# -46342_21-004_3_8.net
KiCad netlist of a schematic drawn in Altium Designer
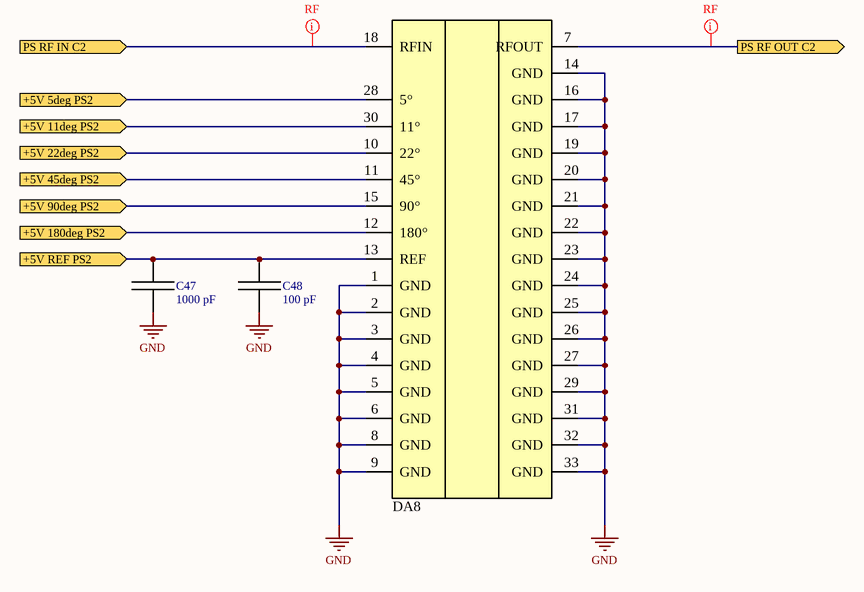
[diagram p0: МПСУ-46342.21-004 Э3 Лист8.SchDoc]

(export (version "E")
  (design (tool "Eeschema 10.0.6"))
  (components
    (comp (ref "C47")
      (value "1000 pF")
      (footprint "CAPC100X50X55L20N")
      (description "Capacitor, generic")
      (fields (field (name "TOLERANCE") "5 %"))
      (libsource (lib "StudentsLibrary") (part "Capacitor"))
    )
    (comp (ref "C48")
      (value "100 pF")
      (footprint "CAPC100X50X55L20N")
      (description "Capacitor, generic")
      (fields (field (name "TOLERANCE") "5 %"))
      (libsource (lib "StudentsLibrary") (part "Capacitor"))
    )
    (comp (ref "DA8")
      (value "TGP2105-SM")
      (footprint "QFN33P50_500X500X80L46X25T340N")
      (description "6 - 18 GHz 6-Bit Digital Phase Shifter (+Vc)")
      (fields (field (name "MANUFACTURER") "Qorvo"))
      (libsource (lib "receiver") (part "TGP2105-SM 1"))
    )
  )
  (nets
    (net (code "1") (name "/+5V 5deg PS2") (class "Default")
      (node (ref "DA8") (pin "28") (pinfunction "5°_28") (pintype "passive"))
    )
    (net (code "2") (name "/+5V 11deg PS2") (class "Default")
      (node (ref "DA8") (pin "30") (pinfunction "11°_30") (pintype "passive"))
    )
    (net (code "3") (name "/+5V 22deg PS2") (class "Default")
      (node (ref "DA8") (pin "10") (pinfunction "22°_10") (pintype "passive"))
    )
    (net (code "4") (name "/+5V 45deg PS2") (class "Default")
      (node (ref "DA8") (pin "11") (pinfunction "45°_11") (pintype "passive"))
    )
    (net (code "5") (name "/+5V 90deg PS2") (class "Default")
      (node (ref "DA8") (pin "15") (pinfunction "90°_15") (pintype "passive"))
    )
    (net (code "6") (name "/+5V 180deg PS2") (class "Default")
      (node (ref "DA8") (pin "12") (pinfunction "180°_12") (pintype "passive"))
    )
    (net (code "7") (name "/+5V REF PS2") (class "Default")
      (node (ref "C47") (pin "2") (pinfunction "2_2") (pintype "passive"))
      (node (ref "C48") (pin "2") (pinfunction "2_2") (pintype "passive"))
      (node (ref "DA8") (pin "13") (pinfunction "REF_13") (pintype "passive"))
    )
    (net (code "8") (name "/PS RF IN C2") (class "Default")
      (node (ref "DA8") (pin "18") (pinfunction "RFIN_18") (pintype "passive"))
    )
    (net (code "9") (name "/PS RF OUT C2") (class "Default")
      (node (ref "DA8") (pin "7") (pinfunction "RFOUT_7") (pintype "passive"))
    )
    (net (code "10") (name "GND") (class "Default")
      (node (ref "C47") (pin "1") (pinfunction "1_1") (pintype "passive"))
      (node (ref "C48") (pin "1") (pinfunction "1_1") (pintype "passive"))
      (node (ref "DA8") (pin "1") (pinfunction "GND_1") (pintype "passive"))
      (node (ref "DA8") (pin "14") (pinfunction "GND_14") (pintype "passive"))
      (node (ref "DA8") (pin "16") (pinfunction "GND_16") (pintype "passive"))
      (node (ref "DA8") (pin "17") (pinfunction "GND_17") (pintype "passive"))
      (node (ref "DA8") (pin "19") (pinfunction "GND_19") (pintype "passive"))
      (node (ref "DA8") (pin "2") (pinfunction "GND_2") (pintype "passive"))
      (node (ref "DA8") (pin "20") (pinfunction "GND_20") (pintype "passive"))
      (node (ref "DA8") (pin "21") (pinfunction "GND_21") (pintype "passive"))
      (node (ref "DA8") (pin "22") (pinfunction "GND_22") (pintype "passive"))
      (node (ref "DA8") (pin "23") (pinfunction "GND_23") (pintype "passive"))
      (node (ref "DA8") (pin "24") (pinfunction "GND_24") (pintype "passive"))
      (node (ref "DA8") (pin "25") (pinfunction "GND_25") (pintype "passive"))
      (node (ref "DA8") (pin "26") (pinfunction "GND_26") (pintype "passive"))
      (node (ref "DA8") (pin "27") (pinfunction "GND_27") (pintype "passive"))
      (node (ref "DA8") (pin "29") (pinfunction "GND_29") (pintype "passive"))
      (node (ref "DA8") (pin "3") (pinfunction "GND_3") (pintype "passive"))
      (node (ref "DA8") (pin "31") (pinfunction "GND_31") (pintype "passive"))
      (node (ref "DA8") (pin "32") (pinfunction "GND_32") (pintype "passive"))
      (node (ref "DA8") (pin "33") (pinfunction "GND_33") (pintype "passive"))
      (node (ref "DA8") (pin "4") (pinfunction "GND_4") (pintype "passive"))
      (node (ref "DA8") (pin "5") (pinfunction "GND_5") (pintype "passive"))
      (node (ref "DA8") (pin "6") (pinfunction "GND_6") (pintype "passive"))
      (node (ref "DA8") (pin "8") (pinfunction "GND_8") (pintype "passive"))
      (node (ref "DA8") (pin "9") (pinfunction "GND_9") (pintype "passive"))
    )
  )
)
